# design.net
KiCad netlist of a schematic drawn in Altium Designer
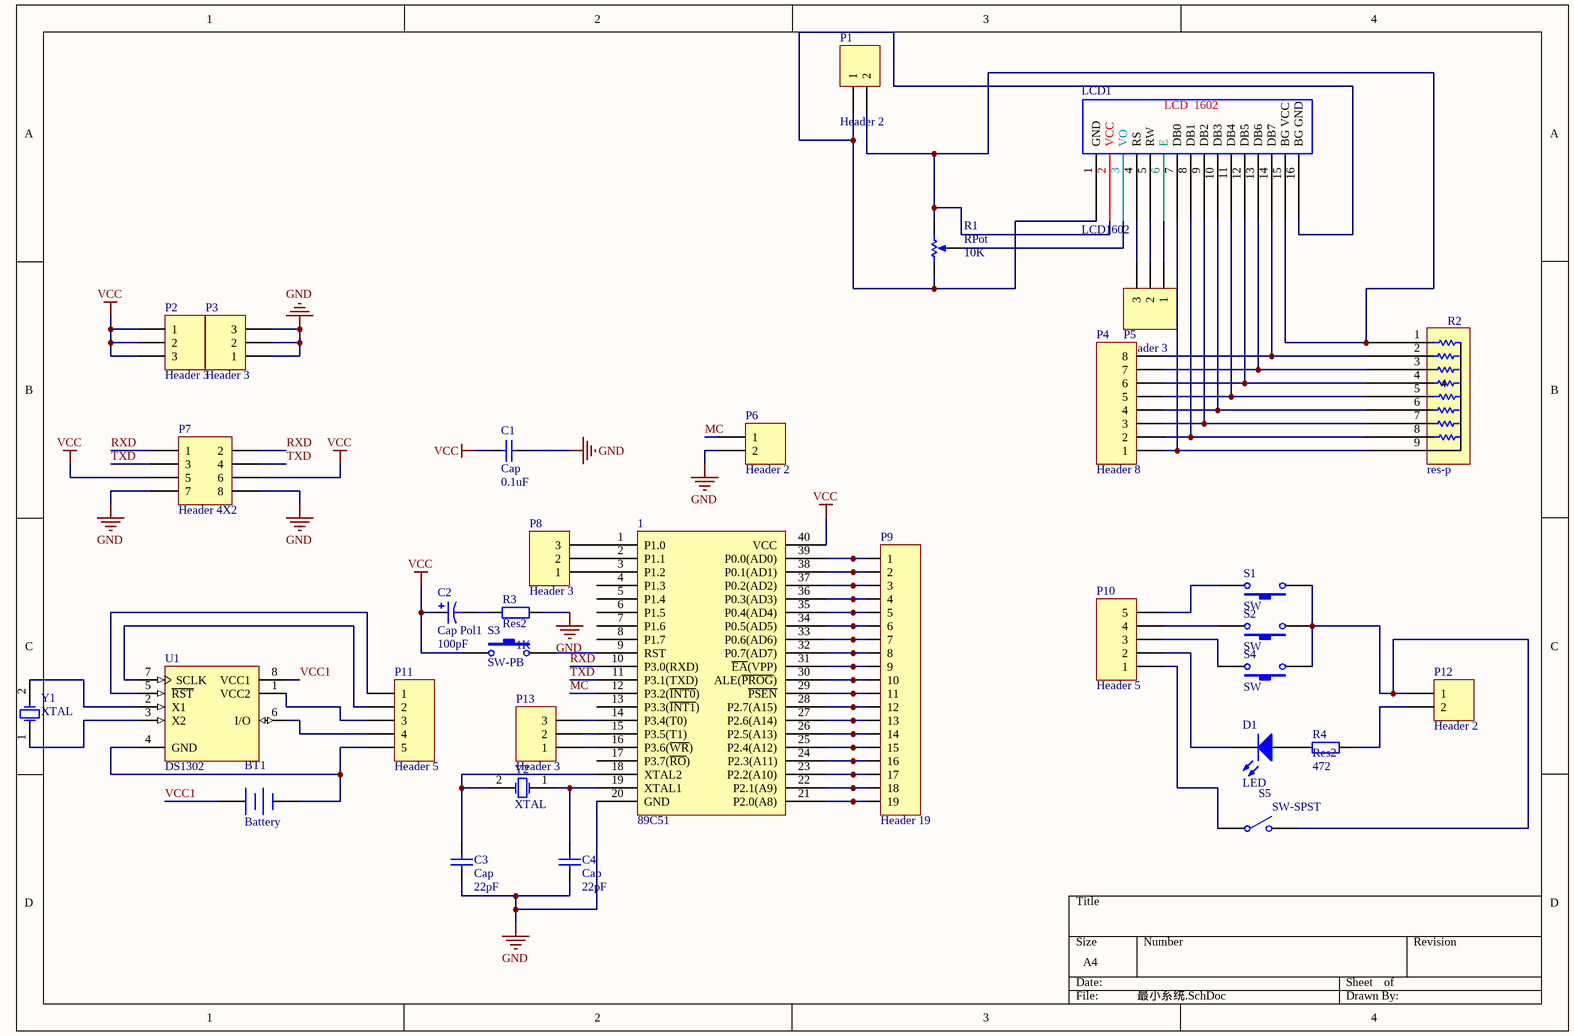
[diagram p0: 最小系统.SchDoc]

(export (version "E")
  (design (tool "Eeschema 10.0.6"))
  (components
    (comp (ref "1") (value "89C51") (libsource (lib "51单片机") (part "89C51")))
    (comp (ref "BT1")
      (value "Battery")
      (footprint "BAT-2")
      (description "Multicell Battery")
      (fields (field (name "PUBLISHER") "Altium Limited"))
      (libsource (lib "Miscellaneous Devices") (part "Battery"))
    )
    (comp (ref "C1")
      (value "Cap")
      (footprint "RAD-0.3")
      (description "Capacitor")
      (fields (field (name "ALTIUM_VALUE") "0.1uF") (field (name "PUBLISHER") "Altium Limited"))
      (libsource (lib "Miscellaneous Devices") (part "Cap"))
    )
    (comp (ref "C2")
      (value "Cap Pol1")
      (footprint "CAPPR1.27-1.7x2.8")
      (description "Polarized Capacitor (Radial)")
      (fields (field (name "ALTIUM_VALUE") "100pF") (field (name "PUBLISHER") "Altium Limited"))
      (libsource (lib "Miscellaneous Devices") (part "Cap Pol1"))
    )
    (comp (ref "C3")
      (value "Cap")
      (footprint "CAPR2.54-5.1x3.2")
      (description "Capacitor")
      (fields (field (name "ALTIUM_VALUE") "22pF") (field (name "PUBLISHER") "Altium Limited"))
      (libsource (lib "Miscellaneous Devices") (part "Cap"))
    )
    (comp (ref "C4")
      (value "Cap")
      (footprint "CAPR2.54-5.1x3.2")
      (description "Capacitor")
      (fields (field (name "ALTIUM_VALUE") "22pF") (field (name "PUBLISHER") "Altium Limited"))
      (libsource (lib "Miscellaneous Devices") (part "Cap"))
    )
    (comp (ref "D1") (value "LED") (footprint "LED-1") (libsource (lib "我的集成库库") (part "LED")))
    (comp (ref "LCD1") (value "LCD1602") (footprint "1602LCD") (libsource (lib "MyInt_Lib") (part "LCD1602")))
    (comp (ref "P1")
      (value "Header 2")
      (footprint "HDR1X2")
      (description "Header, 2-Pin")
      (fields (field (name "PUBLISHER") "Altium Limited"))
      (libsource (lib "") (part "Header 2_1"))
    )
    (comp (ref "P2")
      (value "Header 3")
      (footprint "HDR1X3")
      (description "Header, 3-Pin")
      (fields (field (name "PUBLISHER") "Altium Limited"))
      (libsource (lib "") (part "Header 3_2"))
    )
    (comp (ref "P3")
      (value "Header 3")
      (footprint "HDR1X3")
      (description "Header, 3-Pin")
      (fields (field (name "PUBLISHER") "Altium Limited"))
      (libsource (lib "Miscellaneous Connectors") (part "Header 3"))
    )
    (comp (ref "P4")
      (value "Header 8")
      (footprint "HDR1X8")
      (description "Header, 8-Pin")
      (fields (field (name "PUBLISHER") "Altium Limited"))
      (libsource (lib "Miscellaneous Connectors") (part "Header 8"))
    )
    (comp (ref "P5")
      (value "Header 3")
      (footprint "HDR1X3")
      (description "Header, 3-Pin")
      (fields (field (name "PUBLISHER") "Altium Limited"))
      (libsource (lib "") (part "Header 3_1"))
    )
    (comp (ref "P6")
      (value "Header 2")
      (footprint "HDR1X2")
      (description "Header, 2-Pin")
      (fields (field (name "PUBLISHER") "Altium Limited"))
      (libsource (lib "Miscellaneous Connectors") (part "Header 2"))
    )
    (comp (ref "P7")
      (value "Header 4X2")
      (footprint "HDR2X4")
      (description "Header, 4-Pin, Dual row")
      (fields (field (name "PUBLISHER") "Altium Limited"))
      (libsource (lib "Miscellaneous Connectors") (part "Header 4X2"))
    )
    (comp (ref "P8")
      (value "Header 3")
      (footprint "HDR1X3")
      (description "Header, 3-Pin")
      (fields (field (name "PUBLISHER") "Altium Limited"))
      (libsource (lib "Miscellaneous Connectors") (part "Header 3"))
    )
    (comp (ref "P9")
      (value "Header 19")
      (footprint "HDR1X19")
      (description "Header, 19-Pin")
      (fields (field (name "PUBLISHER") "Altium Limited"))
      (libsource (lib "Miscellaneous Connectors") (part "Header 19"))
    )
    (comp (ref "P10")
      (value "Header 5")
      (footprint "HDR1X5")
      (description "Header, 5-Pin")
      (fields (field (name "PUBLISHER") "Altium Limited"))
      (libsource (lib "Miscellaneous Connectors") (part "Header 5"))
    )
    (comp (ref "P11")
      (value "Header 5")
      (footprint "HDR1X5")
      (description "Header, 5-Pin")
      (fields (field (name "PUBLISHER") "Altium Limited"))
      (libsource (lib "") (part "Header 5_1"))
    )
    (comp (ref "P12")
      (value "Header 2")
      (footprint "HDR1X2")
      (description "Header, 2-Pin")
      (fields (field (name "PUBLISHER") "Altium Limited"))
      (libsource (lib "Miscellaneous Connectors") (part "Header 2"))
    )
    (comp (ref "P13")
      (value "Header 3")
      (footprint "HDR1X3")
      (description "Header, 3-Pin")
      (fields (field (name "PUBLISHER") "Altium Limited"))
      (libsource (lib "Miscellaneous Connectors") (part "Header 3"))
    )
    (comp (ref "R1")
      (value "RPot")
      (footprint "VR5")
      (description "Potentiometer")
      (fields (field (name "ALTIUM_VALUE") "10K") (field (name "PUBLISHER") "Altium Limited"))
      (libsource (lib "Miscellaneous Devices") (part "RPot"))
    )
    (comp (ref "R2") (value "res-p") (footprint "HDR1X9") (libsource (lib "我的集成库库") (part "res-p")))
    (comp (ref "R3")
      (value "Res2")
      (footprint "AXIAL-0.4")
      (description "Resistor")
      (fields (field (name "ALTIUM_VALUE") "1K") (field (name "PUBLISHER") "Altium Limited"))
      (libsource (lib "Miscellaneous Devices") (part "Res2"))
    )
    (comp (ref "R4")
      (value "Res2")
      (footprint "AXIAL-0.4")
      (description "Resistor")
      (fields (field (name "ALTIUM_VALUE") "472") (field (name "PUBLISHER") "Altium Limited"))
      (libsource (lib "Miscellaneous Devices") (part "Res2"))
    )
    (comp (ref "S1") (value "SW") (footprint "SW/PB-V4/H7.1") (libsource (lib "我的集成库库") (part "SWITCH")))
    (comp (ref "S2") (value "SW") (footprint "SW/PB-V4/H7.1") (libsource (lib "我的集成库库") (part "SWITCH")))
    (comp (ref "S3")
      (value "SW-PB")
      (footprint "SW/PB-V4/H7.1")
      (description "Switch")
      (fields (field (name "PUBLISHER") "Altium Limited"))
      (libsource (lib "Miscellaneous Devices") (part "SW-PB"))
    )
    (comp (ref "S4") (value "SW") (footprint "SW/PB-V4/H7.1") (libsource (lib "我的集成库库") (part "SWITCH")))
    (comp (ref "S5")
      (value "SW-SPST")
      (footprint "SPST-2")
      (description "Single-Pole, Single-Throw Switch")
      (fields (field (name "PUBLISHER") "Altium Limited"))
      (libsource (lib "Miscellaneous Devices") (part "SW-SPST"))
    )
    (comp (ref "U1")
      (value "DS1302")
      (footprint "DIP8")
      (description "Trickle Charge Timekeeping Chip")
      (fields (field (name "PUBLISHER") "Altium Limited"))
      (libsource (lib "Dallas Peripheral Real Time Clock") (part "DS1302"))
    )
    (comp (ref "Y1")
      (value "XTAL")
      (footprint "BCY-W2/D3.1")
      (description "Crystal Oscillator")
      (fields (field (name "PUBLISHER") "Altium Limited"))
      (libsource (lib "Miscellaneous Devices") (part "XTAL"))
    )
    (comp (ref "Y2")
      (value "XTAL")
      (footprint "BCY-W2/D3.1")
      (description "Crystal Oscillator")
      (fields (field (name "PUBLISHER") "Altium Limited"))
      (libsource (lib "Miscellaneous Devices") (part "XTAL"))
    )
  )
  (nets
    (net (code "1") (name "/MC") (class "Default")
      (node (ref "1") (pin "12") (pinfunction "P3.2(~{INT0})_12") (pintype "passive"))
      (node (ref "P6") (pin "1") (pinfunction "1_1") (pintype "passive"))
    )
    (net (code "2") (name "/RXD") (class "Default")
      (node (ref "1") (pin "10") (pinfunction "P3.0(RXD)_10") (pintype "passive"))
      (node (ref "P7") (pin "1") (pinfunction "1_1") (pintype "passive"))
      (node (ref "P7") (pin "2") (pinfunction "2_2") (pintype "passive"))
    )
    (net (code "3") (name "/TXD") (class "Default")
      (node (ref "1") (pin "11") (pinfunction "P3.1(TXD)_11") (pintype "passive"))
      (node (ref "P7") (pin "3") (pinfunction "3_3") (pintype "passive"))
      (node (ref "P7") (pin "4") (pinfunction "4_4") (pintype "passive"))
    )
    (net (code "4") (name "/VCC1") (class "Default")
      (node (ref "BT1") (pin "1") (pinfunction "+_1") (pintype "passive"))
      (node (ref "U1") (pin "8") (pinfunction "VCC1_8") (pintype "power_in"))
    )
    (net (code "5") (name "GND") (class "Default")
      (node (ref "1") (pin "20") (pinfunction "GND_20") (pintype "passive"))
      (node (ref "C1") (pin "2") (pinfunction "2_2") (pintype "passive"))
      (node (ref "C3") (pin "2") (pinfunction "2_2") (pintype "passive"))
      (node (ref "C4") (pin "2") (pinfunction "2_2") (pintype "passive"))
      (node (ref "P3") (pin "1") (pinfunction "1_1") (pintype "passive"))
      (node (ref "P3") (pin "2") (pinfunction "2_2") (pintype "passive"))
      (node (ref "P3") (pin "3") (pinfunction "3_3") (pintype "passive"))
      (node (ref "P6") (pin "2") (pinfunction "2_2") (pintype "passive"))
      (node (ref "P7") (pin "7") (pinfunction "7_7") (pintype "passive"))
      (node (ref "P7") (pin "8") (pinfunction "8_8") (pintype "passive"))
      (node (ref "R3") (pin "2") (pinfunction "2_2") (pintype "passive"))
    )
    (net (code "6") (name "Net-(1-ALE(~{PROG}))") (class "Default")
      (node (ref "1") (pin "30") (pinfunction "ALE(~{PROG})_30") (pintype "passive"))
      (node (ref "P9") (pin "10") (pinfunction "10_10") (pintype "passive"))
    )
    (net (code "7") (name "Net-(1-P0.0(AD0))") (class "Default")
      (node (ref "1") (pin "39") (pinfunction "P0.0(AD0)_39") (pintype "passive"))
      (node (ref "P9") (pin "1") (pinfunction "1_1") (pintype "passive"))
    )
    (net (code "8") (name "Net-(1-P0.1(AD1))") (class "Default")
      (node (ref "1") (pin "38") (pinfunction "P0.1(AD1)_38") (pintype "passive"))
      (node (ref "P9") (pin "2") (pinfunction "2_2") (pintype "passive"))
    )
    (net (code "9") (name "Net-(1-P0.2(AD2))") (class "Default")
      (node (ref "1") (pin "37") (pinfunction "P0.2(AD2)_37") (pintype "passive"))
      (node (ref "P9") (pin "3") (pinfunction "3_3") (pintype "passive"))
    )
    (net (code "10") (name "Net-(1-P0.3(AD3))") (class "Default")
      (node (ref "1") (pin "36") (pinfunction "P0.3(AD3)_36") (pintype "passive"))
      (node (ref "P9") (pin "4") (pinfunction "4_4") (pintype "passive"))
    )
    (net (code "11") (name "Net-(1-P0.4(AD4))") (class "Default")
      (node (ref "1") (pin "35") (pinfunction "P0.4(AD4)_35") (pintype "passive"))
      (node (ref "P9") (pin "5") (pinfunction "5_5") (pintype "passive"))
    )
    (net (code "12") (name "Net-(1-P0.5(AD5))") (class "Default")
      (node (ref "1") (pin "34") (pinfunction "P0.5(AD5)_34") (pintype "passive"))
      (node (ref "P9") (pin "6") (pinfunction "6_6") (pintype "passive"))
    )
    (net (code "13") (name "Net-(1-P0.6(AD6))") (class "Default")
      (node (ref "1") (pin "33") (pinfunction "P0.6(AD6)_33") (pintype "passive"))
      (node (ref "P9") (pin "7") (pinfunction "7_7") (pintype "passive"))
    )
    (net (code "14") (name "Net-(1-P0.7(AD7))") (class "Default")
      (node (ref "1") (pin "32") (pinfunction "P0.7(AD7)_32") (pintype "passive"))
      (node (ref "P9") (pin "8") (pinfunction "8_8") (pintype "passive"))
    )
    (net (code "15") (name "Net-(1-P1.0)") (class "Default")
      (node (ref "1") (pin "1") (pinfunction "P1.0_1") (pintype "passive"))
      (node (ref "P8") (pin "3") (pinfunction "3_3") (pintype "passive"))
    )
    (net (code "16") (name "Net-(1-P1.1)") (class "Default")
      (node (ref "1") (pin "2") (pinfunction "P1.1_2") (pintype "passive"))
      (node (ref "P8") (pin "2") (pinfunction "2_2") (pintype "passive"))
    )
    (net (code "17") (name "Net-(1-P1.2)") (class "Default")
      (node (ref "1") (pin "3") (pinfunction "P1.2_3") (pintype "passive"))
      (node (ref "P8") (pin "1") (pinfunction "1_1") (pintype "passive"))
    )
    (net (code "18") (name "Net-(1-P2.0(A8))") (class "Default")
      (node (ref "1") (pin "21") (pinfunction "P2.0(A8)_21") (pintype "passive"))
      (node (ref "P9") (pin "19") (pinfunction "19_19") (pintype "passive"))
    )
    (net (code "19") (name "Net-(1-P2.1(A9))") (class "Default")
      (node (ref "1") (pin "22") (pinfunction "P2.1(A9)_22") (pintype "passive"))
      (node (ref "P9") (pin "18") (pinfunction "18_18") (pintype "passive"))
    )
    (net (code "20") (name "Net-(1-P2.2(A10))") (class "Default")
      (node (ref "1") (pin "23") (pinfunction "P2.2(A10)_23") (pintype "passive"))
      (node (ref "P9") (pin "17") (pinfunction "17_17") (pintype "passive"))
    )
    (net (code "21") (name "Net-(1-P2.3(A11))") (class "Default")
      (node (ref "1") (pin "24") (pinfunction "P2.3(A11)_24") (pintype "passive"))
      (node (ref "P9") (pin "16") (pinfunction "16_16") (pintype "passive"))
    )
    (net (code "22") (name "Net-(1-P2.4(A12))") (class "Default")
      (node (ref "1") (pin "25") (pinfunction "P2.4(A12)_25") (pintype "passive"))
      (node (ref "P9") (pin "15") (pinfunction "15_15") (pintype "passive"))
    )
    (net (code "23") (name "Net-(1-P2.5(A13))") (class "Default")
      (node (ref "1") (pin "26") (pinfunction "P2.5(A13)_26") (pintype "passive"))
      (node (ref "P9") (pin "14") (pinfunction "14_14") (pintype "passive"))
    )
    (net (code "24") (name "Net-(1-P2.6(A14))") (class "Default")
      (node (ref "1") (pin "27") (pinfunction "P2.6(A14)_27") (pintype "passive"))
      (node (ref "P9") (pin "13") (pinfunction "13_13") (pintype "passive"))
    )
    (net (code "25") (name "Net-(1-P2.7(A15))") (class "Default")
      (node (ref "1") (pin "28") (pinfunction "P2.7(A15)_28") (pintype "passive"))
      (node (ref "P9") (pin "12") (pinfunction "12_12") (pintype "passive"))
    )
    (net (code "26") (name "Net-(1-P3.4(T0))") (class "Default")
      (node (ref "1") (pin "14") (pinfunction "P3.4(T0)_14") (pintype "passive"))
      (node (ref "P13") (pin "3") (pinfunction "3_3") (pintype "passive"))
    )
    (net (code "27") (name "Net-(1-P3.5(T1))") (class "Default")
      (node (ref "1") (pin "15") (pinfunction "P3.5(T1)_15") (pintype "passive"))
      (node (ref "P13") (pin "2") (pinfunction "2_2") (pintype "passive"))
    )
    (net (code "28") (name "Net-(1-P3.6(~{WR}))") (class "Default")
      (node (ref "1") (pin "16") (pinfunction "P3.6(~{WR})_16") (pintype "passive"))
      (node (ref "P13") (pin "1") (pinfunction "1_1") (pintype "passive"))
    )
    (net (code "29") (name "Net-(1-RST)") (class "Default")
      (node (ref "1") (pin "9") (pinfunction "RST_9") (pintype "passive"))
      (node (ref "S3") (pin "2") (pinfunction "2_2") (pintype "passive"))
    )
    (net (code "30") (name "Net-(1-XTAL1)") (class "Default")
      (node (ref "1") (pin "19") (pinfunction "XTAL1_19") (pintype "passive"))
      (node (ref "C4") (pin "1") (pinfunction "1_1") (pintype "passive"))
      (node (ref "Y2") (pin "1") (pinfunction "OSC1_1") (pintype "passive"))
    )
    (net (code "31") (name "Net-(1-XTAL2)") (class "Default")
      (node (ref "1") (pin "18") (pinfunction "XTAL2_18") (pintype "passive"))
      (node (ref "C3") (pin "1") (pinfunction "1_1") (pintype "passive"))
      (node (ref "Y2") (pin "2") (pinfunction "OSC2_2") (pintype "passive"))
    )
    (net (code "32") (name "Net-(1-~{EA}(VPP))") (class "Default")
      (node (ref "1") (pin "31") (pinfunction "~{EA}(VPP)_31") (pintype "passive"))
      (node (ref "P9") (pin "9") (pinfunction "9_9") (pintype "passive"))
    )
    (net (code "33") (name "Net-(1-~{PSEN})") (class "Default")
      (node (ref "1") (pin "29") (pinfunction "~{PSEN}_29") (pintype "passive"))
      (node (ref "P9") (pin "11") (pinfunction "11_11") (pintype "passive"))
    )
    (net (code "34") (name "Net-(BT1--)") (class "Default")
      (node (ref "BT1") (pin "2") (pinfunction "-_2") (pintype "passive"))
      (node (ref "P11") (pin "5") (pinfunction "5_5") (pintype "passive"))
      (node (ref "U1") (pin "4") (pinfunction "GND_4") (pintype "power_in"))
    )
    (net (code "35") (name "Net-(C2-Pad2)") (class "Default")
      (node (ref "C2") (pin "2") (pinfunction "2_2") (pintype "passive"))
      (node (ref "R3") (pin "1") (pinfunction "1_1") (pintype "passive"))
    )
    (net (code "36") (name "Net-(D1-A)") (class "Default")
      (node (ref "D1") (pin "1") (pinfunction "A_1") (pintype "passive"))
      (node (ref "R4") (pin "1") (pinfunction "1_1") (pintype "passive"))
    )
    (net (code "37") (name "Net-(D1-K)") (class "Default")
      (node (ref "D1") (pin "2") (pinfunction "K_2") (pintype "passive"))
      (node (ref "P10") (pin "2") (pinfunction "2_2") (pintype "passive"))
    )
    (net (code "38") (name "Net-(LCD1-BG_GND)") (class "Default")
      (node (ref "LCD1") (pin "1") (pinfunction "GND_1") (pintype "passive"))
      (node (ref "LCD1") (pin "16") (pinfunction "BG_GND_16") (pintype "passive"))
      (node (ref "P1") (pin "1") (pinfunction "1_1") (pintype "passive"))
      (node (ref "R1") (pin "1") (pinfunction "TOP_1") (pintype "passive"))
    )
    (net (code "39") (name "Net-(LCD1-BG_VCC)") (class "Default")
      (node (ref "LCD1") (pin "15") (pinfunction "BG_VCC_15") (pintype "passive"))
      (node (ref "LCD1") (pin "2") (pinfunction "VCC_2") (pintype "passive"))
      (node (ref "P1") (pin "2") (pinfunction "2_2") (pintype "passive"))
      (node (ref "R1") (pin "2") (pinfunction "BOT_2") (pintype "passive"))
      (node (ref "R2") (pin "1") (pinfunction "1_1") (pintype "passive"))
    )
    (net (code "40") (name "Net-(LCD1-DB0)") (class "Default")
      (node (ref "LCD1") (pin "7") (pinfunction "DB0_7") (pintype "passive"))
      (node (ref "P4") (pin "1") (pinfunction "1_1") (pintype "passive"))
      (node (ref "R2") (pin "9") (pinfunction "9_9") (pintype "passive"))
    )
    (net (code "41") (name "Net-(LCD1-DB1)") (class "Default")
      (node (ref "LCD1") (pin "8") (pinfunction "DB1_8") (pintype "passive"))
      (node (ref "P4") (pin "2") (pinfunction "2_2") (pintype "passive"))
      (node (ref "R2") (pin "8") (pinfunction "8_8") (pintype "passive"))
    )
    (net (code "42") (name "Net-(LCD1-DB2)") (class "Default")
      (node (ref "LCD1") (pin "9") (pinfunction "DB2_9") (pintype "passive"))
      (node (ref "P4") (pin "3") (pinfunction "3_3") (pintype "passive"))
      (node (ref "R2") (pin "7") (pinfunction "7_7") (pintype "passive"))
    )
    (net (code "43") (name "Net-(LCD1-DB3)") (class "Default")
      (node (ref "LCD1") (pin "10") (pinfunction "DB3_10") (pintype "passive"))
      (node (ref "P4") (pin "4") (pinfunction "4_4") (pintype "passive"))
      (node (ref "R2") (pin "6") (pinfunction "6_6") (pintype "passive"))
    )
    (net (code "44") (name "Net-(LCD1-DB4)") (class "Default")
      (node (ref "LCD1") (pin "11") (pinfunction "DB4_11") (pintype "passive"))
      (node (ref "P4") (pin "5") (pinfunction "5_5") (pintype "passive"))
      (node (ref "R2") (pin "5") (pinfunction "5_5") (pintype "passive"))
    )
    (net (code "45") (name "Net-(LCD1-DB5)") (class "Default")
      (node (ref "LCD1") (pin "12") (pinfunction "DB5_12") (pintype "passive"))
      (node (ref "P4") (pin "6") (pinfunction "6_6") (pintype "passive"))
      (node (ref "R2") (pin "4") (pinfunction "4_4") (pintype "passive"))
    )
    (net (code "46") (name "Net-(LCD1-DB6)") (class "Default")
      (node (ref "LCD1") (pin "13") (pinfunction "DB6_13") (pintype "passive"))
      (node (ref "P4") (pin "7") (pinfunction "7_7") (pintype "passive"))
      (node (ref "R2") (pin "3") (pinfunction "3_3") (pintype "passive"))
    )
    (net (code "47") (name "Net-(LCD1-DB7)") (class "Default")
      (node (ref "LCD1") (pin "14") (pinfunction "DB7_14") (pintype "passive"))
      (node (ref "P4") (pin "8") (pinfunction "8_8") (pintype "passive"))
      (node (ref "R2") (pin "2") (pinfunction "2_2") (pintype "passive"))
    )
    (net (code "48") (name "Net-(LCD1-E)") (class "Default")
      (node (ref "LCD1") (pin "6") (pinfunction "E_6") (pintype "passive"))
      (node (ref "P5") (pin "1") (pinfunction "1_1") (pintype "passive"))
    )
    (net (code "49") (name "Net-(LCD1-RS)") (class "Default")
      (node (ref "LCD1") (pin "4") (pinfunction "RS_4") (pintype "passive"))
      (node (ref "P5") (pin "3") (pinfunction "3_3") (pintype "passive"))
    )
    (net (code "50") (name "Net-(LCD1-RW)") (class "Default")
      (node (ref "LCD1") (pin "5") (pinfunction "RW_5") (pintype "passive"))
      (node (ref "P5") (pin "2") (pinfunction "2_2") (pintype "passive"))
    )
    (net (code "51") (name "Net-(LCD1-VO)") (class "Default")
      (node (ref "LCD1") (pin "3") (pinfunction "VO_3") (pintype "passive"))
      (node (ref "R1") (pin "3") (pinfunction "TAP_3") (pintype "passive"))
    )
    (net (code "52") (name "Net-(P10-Pad3)") (class "Default")
      (node (ref "P10") (pin "3") (pinfunction "3_3") (pintype "passive"))
      (node (ref "S4") (pin "2") (pinfunction "2_2") (pintype "passive"))
    )
    (net (code "53") (name "Net-(P10-Pad4)") (class "Default")
      (node (ref "P10") (pin "4") (pinfunction "4_4") (pintype "passive"))
      (node (ref "S2") (pin "2") (pinfunction "2_2") (pintype "passive"))
    )
    (net (code "54") (name "Net-(P10-Pad5)") (class "Default")
      (node (ref "P10") (pin "5") (pinfunction "5_5") (pintype "passive"))
      (node (ref "S1") (pin "2") (pinfunction "2_2") (pintype "passive"))
    )
    (net (code "55") (name "Net-(P12-Pad2)") (class "Default")
      (node (ref "P12") (pin "2") (pinfunction "2_2") (pintype "passive"))
      (node (ref "R4") (pin "2") (pinfunction "2_2") (pintype "passive"))
    )
    (net (code "56") (name "Net-(S5-COMMON)") (class "Default")
      (node (ref "P10") (pin "1") (pinfunction "1_1") (pintype "passive"))
      (node (ref "S5") (pin "1") (pinfunction "COMMON_1") (pintype "passive"))
    )
    (net (code "57") (name "Net-(S5-NO)") (class "Default")
      (node (ref "P12") (pin "1") (pinfunction "1_1") (pintype "passive"))
      (node (ref "S1") (pin "1") (pinfunction "1_1") (pintype "passive"))
      (node (ref "S2") (pin "1") (pinfunction "1_1") (pintype "passive"))
      (node (ref "S4") (pin "1") (pinfunction "1_1") (pintype "passive"))
      (node (ref "S5") (pin "2") (pinfunction "NO_2") (pintype "passive"))
    )
    (net (code "58") (name "Net-(U1-I{slash}O)") (class "Default")
      (node (ref "P11") (pin "4") (pinfunction "4_4") (pintype "passive"))
      (node (ref "U1") (pin "6") (pinfunction "I/O_6") (pintype "bidirectional"))
    )
    (net (code "59") (name "Net-(U1-SCLK)") (class "Default")
      (node (ref "P11") (pin "2") (pinfunction "2_2") (pintype "passive"))
      (node (ref "U1") (pin "7") (pinfunction "SCLK_7") (pintype "input"))
    )
    (net (code "60") (name "Net-(U1-VCC2)") (class "Default")
      (node (ref "P11") (pin "3") (pinfunction "3_3") (pintype "passive"))
      (node (ref "U1") (pin "1") (pinfunction "VCC2_1") (pintype "power_in"))
    )
    (net (code "61") (name "Net-(U1-X1)") (class "Default")
      (node (ref "U1") (pin "2") (pinfunction "X1_2") (pintype "input"))
      (node (ref "Y1") (pin "2") (pinfunction "OSC2_2") (pintype "passive"))
    )
    (net (code "62") (name "Net-(U1-X2)") (class "Default")
      (node (ref "U1") (pin "3") (pinfunction "X2_3") (pintype "input"))
      (node (ref "Y1") (pin "1") (pinfunction "OSC1_1") (pintype "passive"))
    )
    (net (code "63") (name "Net-(U1-~{RST})") (class "Default")
      (node (ref "P11") (pin "1") (pinfunction "1_1") (pintype "passive"))
      (node (ref "U1") (pin "5") (pinfunction "~{RST}_5") (pintype "input"))
    )
    (net (code "64") (name "VCC") (class "Default")
      (node (ref "1") (pin "40") (pinfunction "VCC_40") (pintype "passive"))
      (node (ref "C1") (pin "1") (pinfunction "1_1") (pintype "passive"))
      (node (ref "C2") (pin "1") (pinfunction "1_1") (pintype "passive"))
      (node (ref "P2") (pin "1") (pinfunction "1_1") (pintype "passive"))
      (node (ref "P2") (pin "2") (pinfunction "2_2") (pintype "passive"))
      (node (ref "P2") (pin "3") (pinfunction "3_3") (pintype "passive"))
      (node (ref "P7") (pin "5") (pinfunction "5_5") (pintype "passive"))
      (node (ref "P7") (pin "6") (pinfunction "6_6") (pintype "passive"))
      (node (ref "S3") (pin "1") (pinfunction "1_1") (pintype "passive"))
    )
    (net (code "65") (name "unconnected-(1-P1.3-Pad4)") (class "Default")
      (node (ref "1") (pin "4") (pinfunction "P1.3_4") (pintype "passive"))
    )
    (net (code "66") (name "unconnected-(1-P1.4-Pad5)") (class "Default")
      (node (ref "1") (pin "5") (pinfunction "P1.4_5") (pintype "passive"))
    )
    (net (code "67") (name "unconnected-(1-P1.5-Pad6)") (class "Default")
      (node (ref "1") (pin "6") (pinfunction "P1.5_6") (pintype "passive"))
    )
    (net (code "68") (name "unconnected-(1-P1.6-Pad7)") (class "Default")
      (node (ref "1") (pin "7") (pinfunction "P1.6_7") (pintype "passive"))
    )
    (net (code "69") (name "unconnected-(1-P1.7-Pad8)") (class "Default")
      (node (ref "1") (pin "8") (pinfunction "P1.7_8") (pintype "passive"))
    )
    (net (code "70") (name "unconnected-(1-P3.3(~{INT1})-Pad13)") (class "Default")
      (node (ref "1") (pin "13") (pinfunction "P3.3(~{INT1})_13") (pintype "passive"))
    )
    (net (code "71") (name "unconnected-(1-P3.7(~{RO})-Pad17)") (class "Default")
      (node (ref "1") (pin "17") (pinfunction "P3.7(~{RO})_17") (pintype "passive"))
    )
  )
)
